# Signal_Isolation.net
KiCad netlist of a schematic drawn in Altium Designer
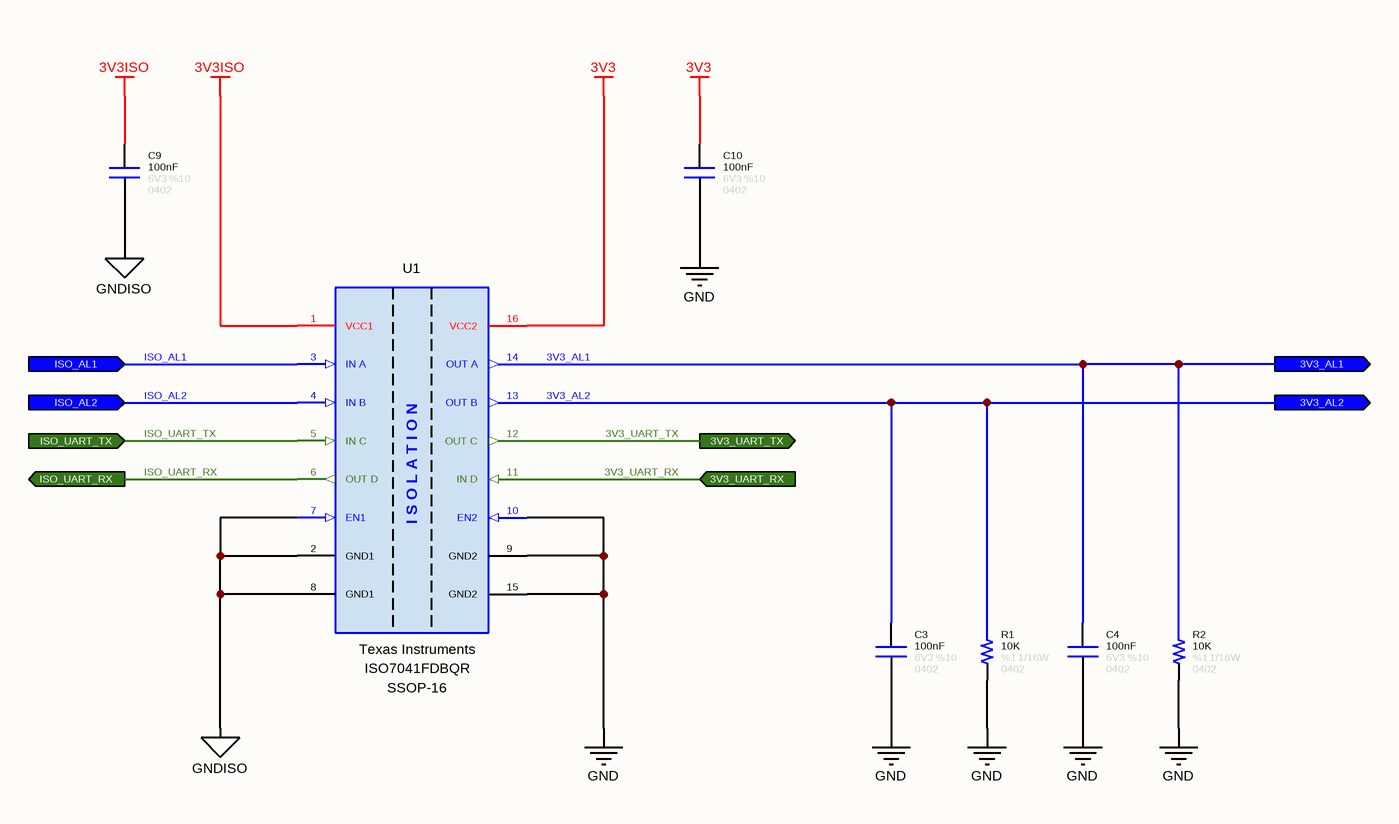
[diagram p0: Signal Isolation.SchDoc]

(export (version "E")
  (design (tool "Eeschema 10.0.6"))
  (components
    (comp (ref "C3")
      (value "100nF")
      (footprint "CAPACITOR_0402")
      (description "Capacitor - 100nF [0402-6V3] (Ceramic)")
      (fields
        (field (name "MANUFACTURER PART NUMBER") "04026D104KAT4A")
        (field (name "TOLERANCE") "%10")
        (field (name "VOLTAGE") "6V3")
        (field (name "CASE") "0402")
        (field (name "Comment") "Capacitor - 100nF [0402] (Ceramic)")
      )
      (libsource (lib "Akkoyun") (part "Capacitor - 100nF [0402-6V3]"))
    )
    (comp (ref "C4")
      (value "100nF")
      (footprint "CAPACITOR_0402")
      (description "Capacitor - 100nF [0402-6V3] (Ceramic)")
      (fields
        (field (name "MANUFACTURER PART NUMBER") "04026D104KAT4A")
        (field (name "TOLERANCE") "%10")
        (field (name "VOLTAGE") "6V3")
        (field (name "CASE") "0402")
        (field (name "Comment") "Capacitor - 100nF [0402] (Ceramic)")
      )
      (libsource (lib "Akkoyun") (part "Capacitor - 100nF [0402-6V3]"))
    )
    (comp (ref "C9")
      (value "100nF")
      (footprint "CAPACITOR_0402")
      (description "Capacitor - 100nF [0402-6V3] (Ceramic)")
      (fields
        (field (name "MANUFACTURER PART NUMBER") "04026D104KAT4A")
        (field (name "TOLERANCE") "%10")
        (field (name "VOLTAGE") "6V3")
        (field (name "CASE") "0402")
        (field (name "Comment") "Capacitor - 100nF [0402] (Ceramic)")
      )
      (libsource (lib "Akkoyun") (part "Capacitor - 100nF [0402-6V3]"))
    )
    (comp (ref "C10")
      (value "100nF")
      (footprint "CAPACITOR_0402")
      (description "Capacitor - 100nF [0402-6V3] (Ceramic)")
      (fields
        (field (name "MANUFACTURER PART NUMBER") "04026D104KAT4A")
        (field (name "TOLERANCE") "%10")
        (field (name "VOLTAGE") "6V3")
        (field (name "CASE") "0402")
        (field (name "Comment") "Capacitor - 100nF [0402] (Ceramic)")
      )
      (libsource (lib "Akkoyun") (part "Capacitor - 100nF [0402-6V3]"))
    )
    (comp (ref "R1")
      (value "10K")
      (footprint "RESISTOR_0402")
      (description "Thick Film Resistors - SMD 1/16 W 10 KOhm 1%")
      (fields
        (field (name "MANUFACTURER PART NUMBER") "CRCW040210K0FKED")
        (field (name "TOLERANCE") "%1")
        (field (name "CASE") "0402")
        (field (name "POWER") "1/16W")
        (field (name "Comment") "10K - 0402 - %1 - 1/16W")
      )
      (libsource (lib "Akkoyun") (part "Resistor - 10K [0402]"))
    )
    (comp (ref "R2")
      (value "10K")
      (footprint "RESISTOR_0402")
      (description "Thick Film Resistors - SMD 1/16 W 10 KOhm 1%")
      (fields
        (field (name "MANUFACTURER PART NUMBER") "CRCW040210K0FKED")
        (field (name "TOLERANCE") "%1")
        (field (name "CASE") "0402")
        (field (name "POWER") "1/16W")
        (field (name "Comment") "10K - 0402 - %1 - 1/16W")
      )
      (libsource (lib "Akkoyun") (part "Resistor - 10K [0402]"))
    )
    (comp (ref "U1")
      (value "ISO7041")
      (footprint "SSOP-16")
      (fields
        (field (name "MANUFACTURER NAME") "Texas Instruments")
        (field (name "MANUFACTURER PART NUMBER") "ISO7041FDBQR")
        (field (name "CASE") "SSOP-16")
      )
      (libsource (lib "Akkoyun") (part "IC - ISO7041"))
    )
  )
  (nets
    (net (code "1") (name "/3V3_AL1") (class "Default")
      (node (ref "C4") (pin "2") (pinfunction "2_2") (pintype "passive"))
      (node (ref "R2") (pin "2") (pinfunction "2_2") (pintype "passive"))
      (node (ref "U1") (pin "14") (pinfunction "OUT_A_14") (pintype "output"))
    )
    (net (code "2") (name "/3V3_AL2") (class "Default")
      (node (ref "C3") (pin "2") (pinfunction "2_2") (pintype "passive"))
      (node (ref "R1") (pin "2") (pinfunction "2_2") (pintype "passive"))
      (node (ref "U1") (pin "13") (pinfunction "OUT_B_13") (pintype "output"))
    )
    (net (code "3") (name "/3V3_UART_RX") (class "Default")
      (node (ref "U1") (pin "11") (pinfunction "IN_D_11") (pintype "input"))
    )
    (net (code "4") (name "/3V3_UART_TX") (class "Default")
      (node (ref "U1") (pin "12") (pinfunction "OUT_C_12") (pintype "output"))
    )
    (net (code "5") (name "/ISO_AL1") (class "Default")
      (node (ref "U1") (pin "3") (pinfunction "IN_A_3") (pintype "input"))
    )
    (net (code "6") (name "/ISO_AL2") (class "Default")
      (node (ref "U1") (pin "4") (pinfunction "IN_B_4") (pintype "input"))
    )
    (net (code "7") (name "/ISO_UART_RX") (class "Default")
      (node (ref "U1") (pin "6") (pinfunction "OUT_D_6") (pintype "output"))
    )
    (net (code "8") (name "/ISO_UART_TX") (class "Default")
      (node (ref "U1") (pin "5") (pinfunction "IN_C_5") (pintype "input"))
    )
    (net (code "9") (name "3V3") (class "Default")
      (node (ref "C10") (pin "2") (pinfunction "2_2") (pintype "passive"))
      (node (ref "U1") (pin "16") (pinfunction "VCC2_16") (pintype "power_in"))
    )
    (net (code "10") (name "3V3ISO") (class "Default")
      (node (ref "C9") (pin "2") (pinfunction "2_2") (pintype "passive"))
      (node (ref "U1") (pin "1") (pinfunction "VCC1_1") (pintype "power_in"))
    )
    (net (code "11") (name "GND") (class "Default")
      (node (ref "C10") (pin "1") (pinfunction "1_1") (pintype "passive"))
      (node (ref "C3") (pin "1") (pinfunction "1_1") (pintype "passive"))
      (node (ref "C4") (pin "1") (pinfunction "1_1") (pintype "passive"))
      (node (ref "R1") (pin "1") (pinfunction "1_1") (pintype "passive"))
      (node (ref "R2") (pin "1") (pinfunction "1_1") (pintype "passive"))
      (node (ref "U1") (pin "10") (pinfunction "EN2_10") (pintype "input"))
      (node (ref "U1") (pin "15") (pinfunction "GND2_15") (pintype "power_in"))
      (node (ref "U1") (pin "9") (pinfunction "GND2_9") (pintype "power_in"))
    )
    (net (code "12") (name "GNDISO") (class "Default")
      (node (ref "C9") (pin "1") (pinfunction "1_1") (pintype "passive"))
      (node (ref "U1") (pin "2") (pinfunction "GND1_2") (pintype "power_in"))
      (node (ref "U1") (pin "7") (pinfunction "EN1_7") (pintype "input"))
      (node (ref "U1") (pin "8") (pinfunction "GND1_8") (pintype "power_in"))
    )
  )
)
